# FULL_WAVE_RECTIFIER_SCHEMATIC.net
KiCad netlist of a schematic drawn in EasyEDA
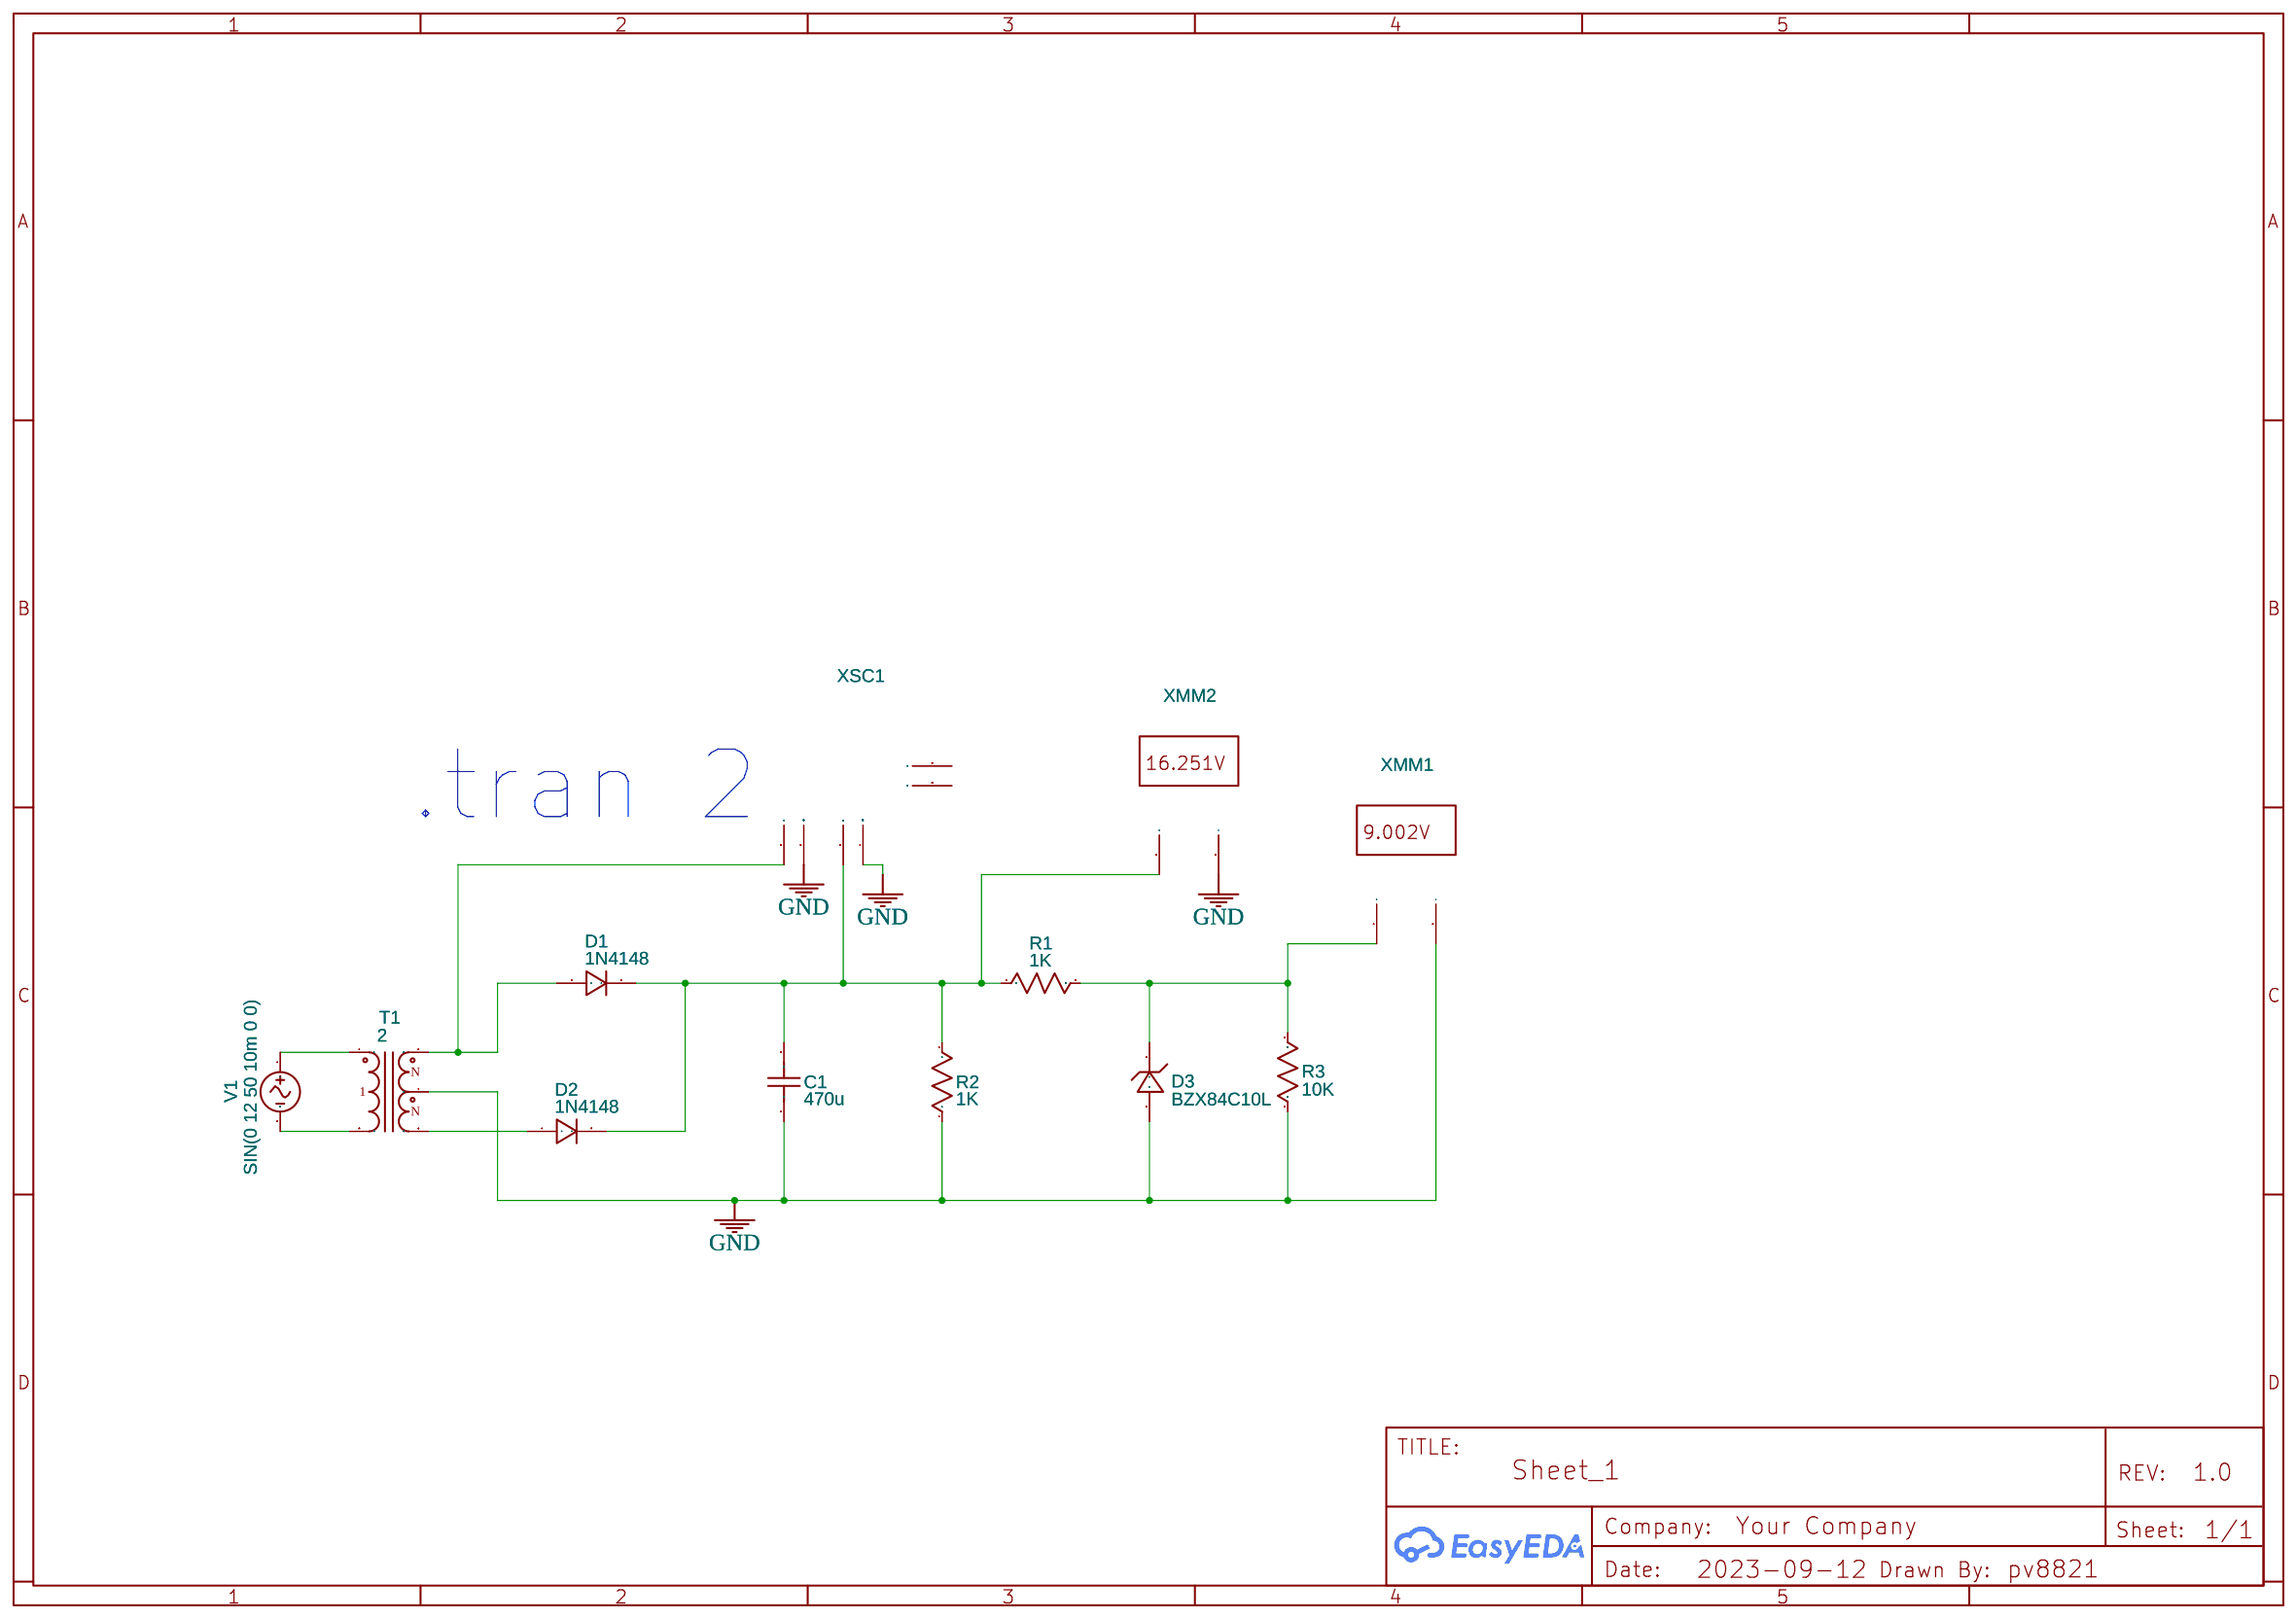
[diagram p0: schematic sheet]

(export (version "E")
  (design (tool "Eeschema 10.0.6"))
  (components
    (comp (ref "C1") (value "470u") (libsource (lib "") (part "Capacitor_US")))
    (comp (ref "D1") (value "1N4148") (libsource (lib "") (part "1N4148")))
    (comp (ref "D2") (value "1N4148") (libsource (lib "") (part "1N4148")))
    (comp (ref "D3") (value "BZX84C10L") (libsource (lib "") (part "BZX84C10L")))
    (comp (ref "R1") (value "1K") (libsource (lib "") (part "Resistor_US_1")))
    (comp (ref "R2") (value "1K") (libsource (lib "") (part "Resistor_US")))
    (comp (ref "R3") (value "10K") (libsource (lib "") (part "Resistor_US")))
    (comp (ref "T1") (value "2") (libsource (lib "") (part "XFMR_TAP")))
    (comp (ref "V1") (value "SIN(0 12 50 10m 0 0)") (libsource (lib "") (part "VSin")))
    (comp (ref "XMM1") (value "Multimeter") (libsource (lib "") (part "MULTIMETER_1")))
    (comp (ref "XMM2") (value "Multimeter") (libsource (lib "") (part "MULTIMETER")))
    (comp (ref "XSC1") (value "Oscilloscope") (libsource (lib "") (part "OSCILLOSCOPE")))
  )
  (nets
    (net (code "1") (name "GND") (class "Default")
      (node (ref "C1") (pin "1") (pinfunction "1_1") (pintype "unspecified"))
      (node (ref "D3") (pin "1") (pinfunction "A_1") (pintype "unspecified"))
      (node (ref "R2") (pin "1") (pinfunction "1_1") (pintype "unspecified"))
      (node (ref "R3") (pin "1") (pinfunction "1_1") (pintype "unspecified"))
      (node (ref "T1") (pin "4") (pinfunction "4_4") (pintype "unspecified"))
      (node (ref "XMM1") (pin "2") (pinfunction "I_2") (pintype "unspecified"))
      (node (ref "XMM2") (pin "2") (pinfunction "I_2") (pintype "unspecified"))
      (node (ref "XSC1") (pin "2") (pinfunction "GND1_2") (pintype "unspecified"))
      (node (ref "XSC1") (pin "4") (pinfunction "GND2_4") (pintype "unspecified"))
    )
    (net (code "2") (name "Net-(D1-A)") (class "Default")
      (node (ref "D1") (pin "1") (pinfunction "A_1") (pintype "unspecified"))
      (node (ref "T1") (pin "5") (pinfunction "5_5") (pintype "unspecified"))
      (node (ref "XSC1") (pin "1") (pinfunction "A_1") (pintype "unspecified"))
    )
    (net (code "3") (name "Net-(D1-K)") (class "Default")
      (node (ref "C1") (pin "2") (pinfunction "2_2") (pintype "unspecified"))
      (node (ref "D1") (pin "2") (pinfunction "K_2") (pintype "unspecified"))
      (node (ref "D2") (pin "2") (pinfunction "K_2") (pintype "unspecified"))
      (node (ref "R1") (pin "1") (pinfunction "1_1") (pintype "unspecified"))
      (node (ref "R2") (pin "2") (pinfunction "2_2") (pintype "unspecified"))
      (node (ref "XMM2") (pin "1") (pinfunction "+_1") (pintype "unspecified"))
      (node (ref "XSC1") (pin "3") (pinfunction "B_3") (pintype "unspecified"))
    )
    (net (code "4") (name "Net-(D2-A)") (class "Default")
      (node (ref "D2") (pin "1") (pinfunction "A_1") (pintype "unspecified"))
      (node (ref "T1") (pin "3") (pinfunction "3_3") (pintype "unspecified"))
    )
    (net (code "5") (name "Net-(D3-K)") (class "Default")
      (node (ref "D3") (pin "2") (pinfunction "K_2") (pintype "unspecified"))
      (node (ref "R1") (pin "2") (pinfunction "2_2") (pintype "unspecified"))
      (node (ref "R3") (pin "2") (pinfunction "2_2") (pintype "unspecified"))
      (node (ref "XMM1") (pin "1") (pinfunction "+_1") (pintype "unspecified"))
    )
    (net (code "6") (name "Net-(T1-Pad1)") (class "Default")
      (node (ref "T1") (pin "1") (pinfunction "1_1") (pintype "unspecified"))
      (node (ref "V1") (pin "1") (pinfunction "1_1") (pintype "unspecified"))
    )
    (net (code "7") (name "Net-(T1-Pad2)") (class "Default")
      (node (ref "T1") (pin "2") (pinfunction "2_2") (pintype "unspecified"))
      (node (ref "V1") (pin "2") (pinfunction "2_2") (pintype "unspecified"))
    )
    (net (code "8") (name "unconnected-(XSC1-T+-Pad5)") (class "Default")
      (node (ref "XSC1") (pin "5") (pinfunction "T+_5") (pintype "unspecified"))
    )
    (net (code "9") (name "unconnected-(XSC1-T--Pad6)") (class "Default")
      (node (ref "XSC1") (pin "6") (pinfunction "T-_6") (pintype "unspecified"))
    )
  )
)
